# FPGA_main.net
KiCad netlist of a schematic drawn in Altium Designer
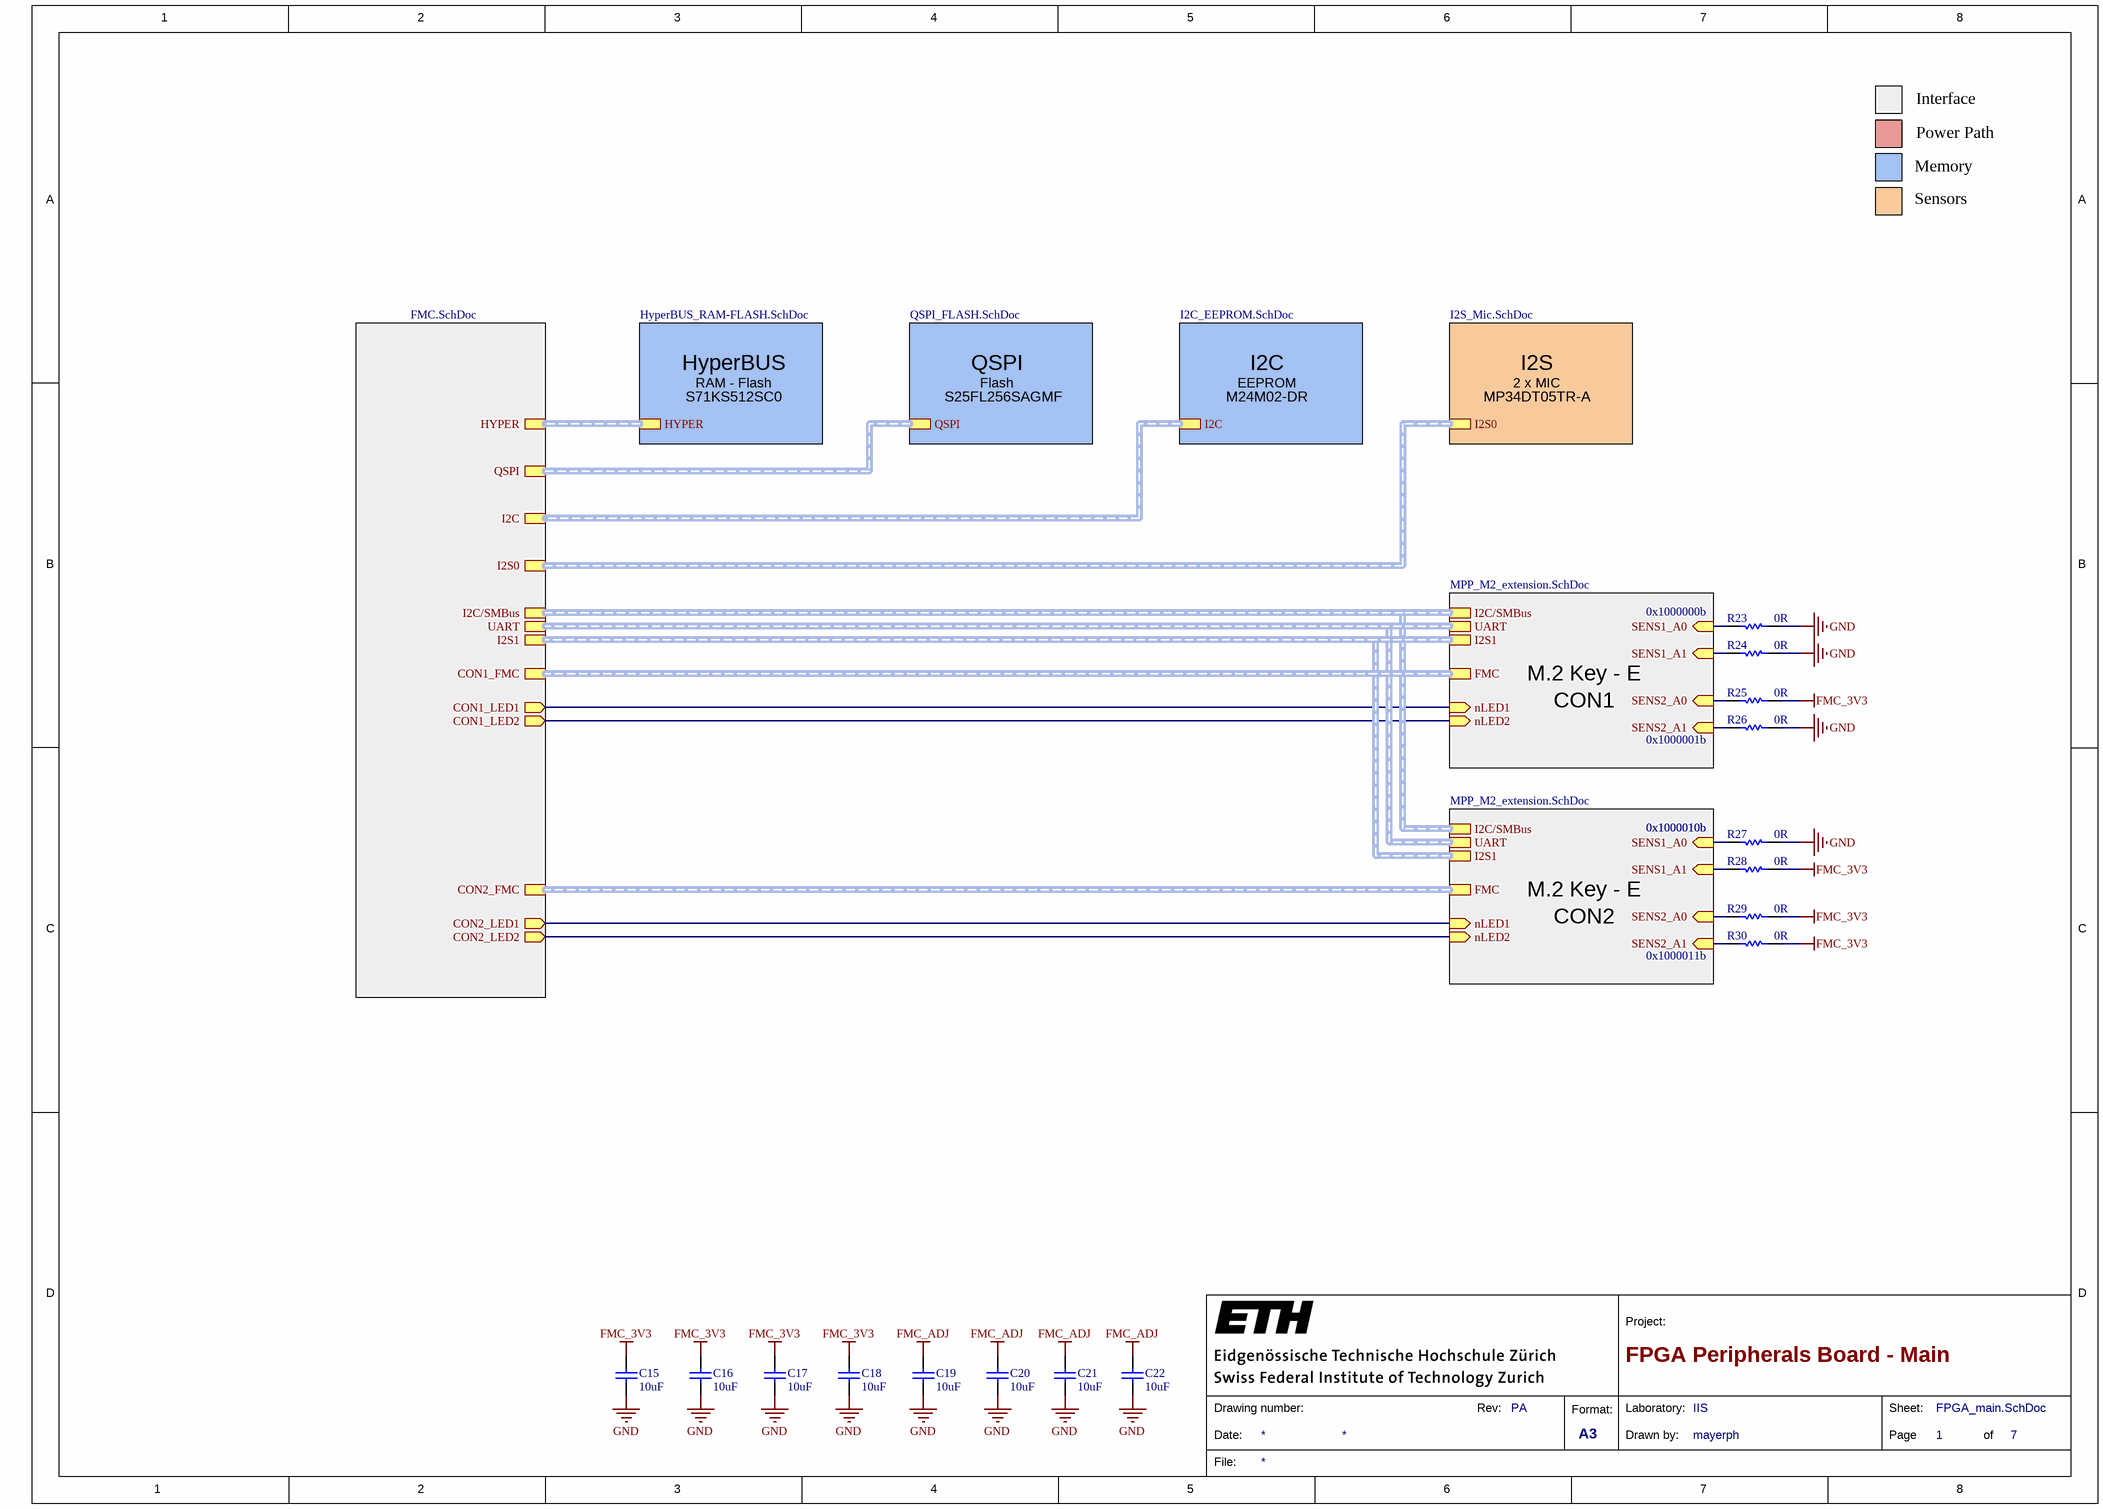
[diagram p0: FPGA_main.SchDoc]

(export (version "E")
  (design (tool "Eeschema 10.0.6"))
  (components
    (comp (ref "C15")
      (value "10uF")
      (footprint "CAPC1608X90X35LL15T15")
      (fields
        (field (name "MANUFACTURER") "AVX Interconnect / Elco")
        (field (name "PART NUMBER") "06036D106MAT2A")
        (field (name "TOLERANCE") "20%")
      )
      (libsource (lib "Altium Content Vault") (part "CAP"))
    )
    (comp (ref "C16")
      (value "10uF")
      (footprint "CAPC1608X90X35LL15T15")
      (fields
        (field (name "MANUFACTURER") "AVX Interconnect / Elco")
        (field (name "PART NUMBER") "06036D106MAT2A")
        (field (name "TOLERANCE") "20%")
      )
      (libsource (lib "Altium Content Vault") (part "CAP"))
    )
    (comp (ref "C17")
      (value "10uF")
      (footprint "CAPC1608X90X35LL15T15")
      (fields
        (field (name "MANUFACTURER") "AVX Interconnect / Elco")
        (field (name "PART NUMBER") "06036D106MAT2A")
        (field (name "TOLERANCE") "20%")
      )
      (libsource (lib "Altium Content Vault") (part "CAP"))
    )
    (comp (ref "C18")
      (value "10uF")
      (footprint "CAPC1608X90X35LL15T15")
      (fields
        (field (name "MANUFACTURER") "AVX Interconnect / Elco")
        (field (name "PART NUMBER") "06036D106MAT2A")
        (field (name "TOLERANCE") "20%")
      )
      (libsource (lib "Altium Content Vault") (part "CAP"))
    )
    (comp (ref "C19")
      (value "10uF")
      (footprint "CAPC1608X90X35LL15T15")
      (fields
        (field (name "MANUFACTURER") "AVX Interconnect / Elco")
        (field (name "PART NUMBER") "06036D106MAT2A")
        (field (name "TOLERANCE") "20%")
      )
      (libsource (lib "Altium Content Vault") (part "CAP"))
    )
    (comp (ref "C20")
      (value "10uF")
      (footprint "CAPC1608X90X35LL15T15")
      (fields
        (field (name "MANUFACTURER") "AVX Interconnect / Elco")
        (field (name "PART NUMBER") "06036D106MAT2A")
        (field (name "TOLERANCE") "20%")
      )
      (libsource (lib "Altium Content Vault") (part "CAP"))
    )
    (comp (ref "C21")
      (value "10uF")
      (footprint "CAPC1608X90X35LL15T15")
      (fields
        (field (name "MANUFACTURER") "AVX Interconnect / Elco")
        (field (name "PART NUMBER") "06036D106MAT2A")
        (field (name "TOLERANCE") "20%")
      )
      (libsource (lib "Altium Content Vault") (part "CAP"))
    )
    (comp (ref "C22")
      (value "10uF")
      (footprint "CAPC1608X90X35LL15T15")
      (fields
        (field (name "MANUFACTURER") "AVX Interconnect / Elco")
        (field (name "PART NUMBER") "06036D106MAT2A")
        (field (name "TOLERANCE") "20%")
      )
      (libsource (lib "Altium Content Vault") (part "CAP"))
    )
    (comp (ref "R23")
      (value "0R")
      (footprint "RESC1005X40X25LL05T10")
      (fields
        (field (name "MANUFACTURER") "Yageo")
        (field (name "PART NUMBER") "RC0402JR-070RL")
        (field (name "TOLERANCE") "5%")
      )
      (libsource (lib "Altium Content Vault") (part "RES"))
    )
    (comp (ref "R24")
      (value "0R")
      (footprint "RESC1005X40X25LL05T10")
      (fields
        (field (name "MANUFACTURER") "Yageo")
        (field (name "PART NUMBER") "RC0402JR-070RL")
        (field (name "TOLERANCE") "5%")
      )
      (libsource (lib "Altium Content Vault") (part "RES"))
    )
    (comp (ref "R25")
      (value "0R")
      (footprint "RESC1005X40X25LL05T10")
      (fields
        (field (name "MANUFACTURER") "Yageo")
        (field (name "PART NUMBER") "RC0402JR-070RL")
        (field (name "TOLERANCE") "5%")
      )
      (libsource (lib "Altium Content Vault") (part "RES"))
    )
    (comp (ref "R26")
      (value "0R")
      (footprint "RESC1005X40X25LL05T10")
      (fields
        (field (name "MANUFACTURER") "Yageo")
        (field (name "PART NUMBER") "RC0402JR-070RL")
        (field (name "TOLERANCE") "5%")
      )
      (libsource (lib "Altium Content Vault") (part "RES"))
    )
    (comp (ref "R27")
      (value "0R")
      (footprint "RESC1005X40X25LL05T10")
      (fields
        (field (name "MANUFACTURER") "Yageo")
        (field (name "PART NUMBER") "RC0402JR-070RL")
        (field (name "TOLERANCE") "5%")
      )
      (libsource (lib "Altium Content Vault") (part "RES"))
    )
    (comp (ref "R28")
      (value "0R")
      (footprint "RESC1005X40X25LL05T10")
      (fields
        (field (name "MANUFACTURER") "Yageo")
        (field (name "PART NUMBER") "RC0402JR-070RL")
        (field (name "TOLERANCE") "5%")
      )
      (libsource (lib "Altium Content Vault") (part "RES"))
    )
    (comp (ref "R29")
      (value "0R")
      (footprint "RESC1005X40X25LL05T10")
      (fields
        (field (name "MANUFACTURER") "Yageo")
        (field (name "PART NUMBER") "RC0402JR-070RL")
        (field (name "TOLERANCE") "5%")
      )
      (libsource (lib "Altium Content Vault") (part "RES"))
    )
    (comp (ref "R30")
      (value "0R")
      (footprint "RESC1005X40X25LL05T10")
      (fields
        (field (name "MANUFACTURER") "Yageo")
        (field (name "PART NUMBER") "RC0402JR-070RL")
        (field (name "TOLERANCE") "5%")
      )
      (libsource (lib "Altium Content Vault") (part "RES"))
    )
  )
  (nets
    (net (code "13") (name "/SENS1_A0") (class "Default")
      (node (ref "R27") (pin "2") (pinfunction "2_2") (pintype "passive"))
    )
    (net (code "14") (name "/SENS1_A0_1") (class "Default")
      (node (ref "R23") (pin "2") (pinfunction "2_2") (pintype "passive"))
    )
    (net (code "15") (name "/SENS1_A1") (class "Default")
      (node (ref "R28") (pin "2") (pinfunction "2_2") (pintype "passive"))
    )
    (net (code "16") (name "/SENS1_A1_1") (class "Default")
      (node (ref "R24") (pin "2") (pinfunction "2_2") (pintype "passive"))
    )
    (net (code "17") (name "/SENS2_A0") (class "Default")
      (node (ref "R29") (pin "2") (pinfunction "2_2") (pintype "passive"))
    )
    (net (code "18") (name "/SENS2_A0_1") (class "Default")
      (node (ref "R25") (pin "2") (pinfunction "2_2") (pintype "passive"))
    )
    (net (code "19") (name "/SENS2_A1") (class "Default")
      (node (ref "R30") (pin "2") (pinfunction "2_2") (pintype "passive"))
    )
    (net (code "20") (name "/SENS2_A1_1") (class "Default")
      (node (ref "R26") (pin "2") (pinfunction "2_2") (pintype "passive"))
    )
    (net (code "22") (name "FMC_3V3") (class "Default")
      (node (ref "C15") (pin "2") (pinfunction "2_2") (pintype "passive"))
      (node (ref "C16") (pin "2") (pinfunction "2_2") (pintype "passive"))
      (node (ref "C17") (pin "2") (pinfunction "2_2") (pintype "passive"))
      (node (ref "C18") (pin "2") (pinfunction "2_2") (pintype "passive"))
      (node (ref "R25") (pin "1") (pinfunction "1_1") (pintype "passive"))
      (node (ref "R28") (pin "1") (pinfunction "1_1") (pintype "passive"))
      (node (ref "R29") (pin "1") (pinfunction "1_1") (pintype "passive"))
      (node (ref "R30") (pin "1") (pinfunction "1_1") (pintype "passive"))
    )
    (net (code "23") (name "FMC_ADJ") (class "Default")
      (node (ref "C19") (pin "2") (pinfunction "2_2") (pintype "passive"))
      (node (ref "C20") (pin "2") (pinfunction "2_2") (pintype "passive"))
      (node (ref "C21") (pin "2") (pinfunction "2_2") (pintype "passive"))
      (node (ref "C22") (pin "2") (pinfunction "2_2") (pintype "passive"))
    )
    (net (code "24") (name "GND") (class "Default")
      (node (ref "C15") (pin "1") (pinfunction "1_1") (pintype "passive"))
      (node (ref "C16") (pin "1") (pinfunction "1_1") (pintype "passive"))
      (node (ref "C17") (pin "1") (pinfunction "1_1") (pintype "passive"))
      (node (ref "C18") (pin "1") (pinfunction "1_1") (pintype "passive"))
      (node (ref "C19") (pin "1") (pinfunction "1_1") (pintype "passive"))
      (node (ref "C20") (pin "1") (pinfunction "1_1") (pintype "passive"))
      (node (ref "C21") (pin "1") (pinfunction "1_1") (pintype "passive"))
      (node (ref "C22") (pin "1") (pinfunction "1_1") (pintype "passive"))
      (node (ref "R23") (pin "1") (pinfunction "1_1") (pintype "passive"))
      (node (ref "R24") (pin "1") (pinfunction "1_1") (pintype "passive"))
      (node (ref "R26") (pin "1") (pinfunction "1_1") (pintype "passive"))
      (node (ref "R27") (pin "1") (pinfunction "1_1") (pintype "passive"))
    )
  )
)
